# schematic.net
KiCad netlist of a schematic drawn in EAGLE
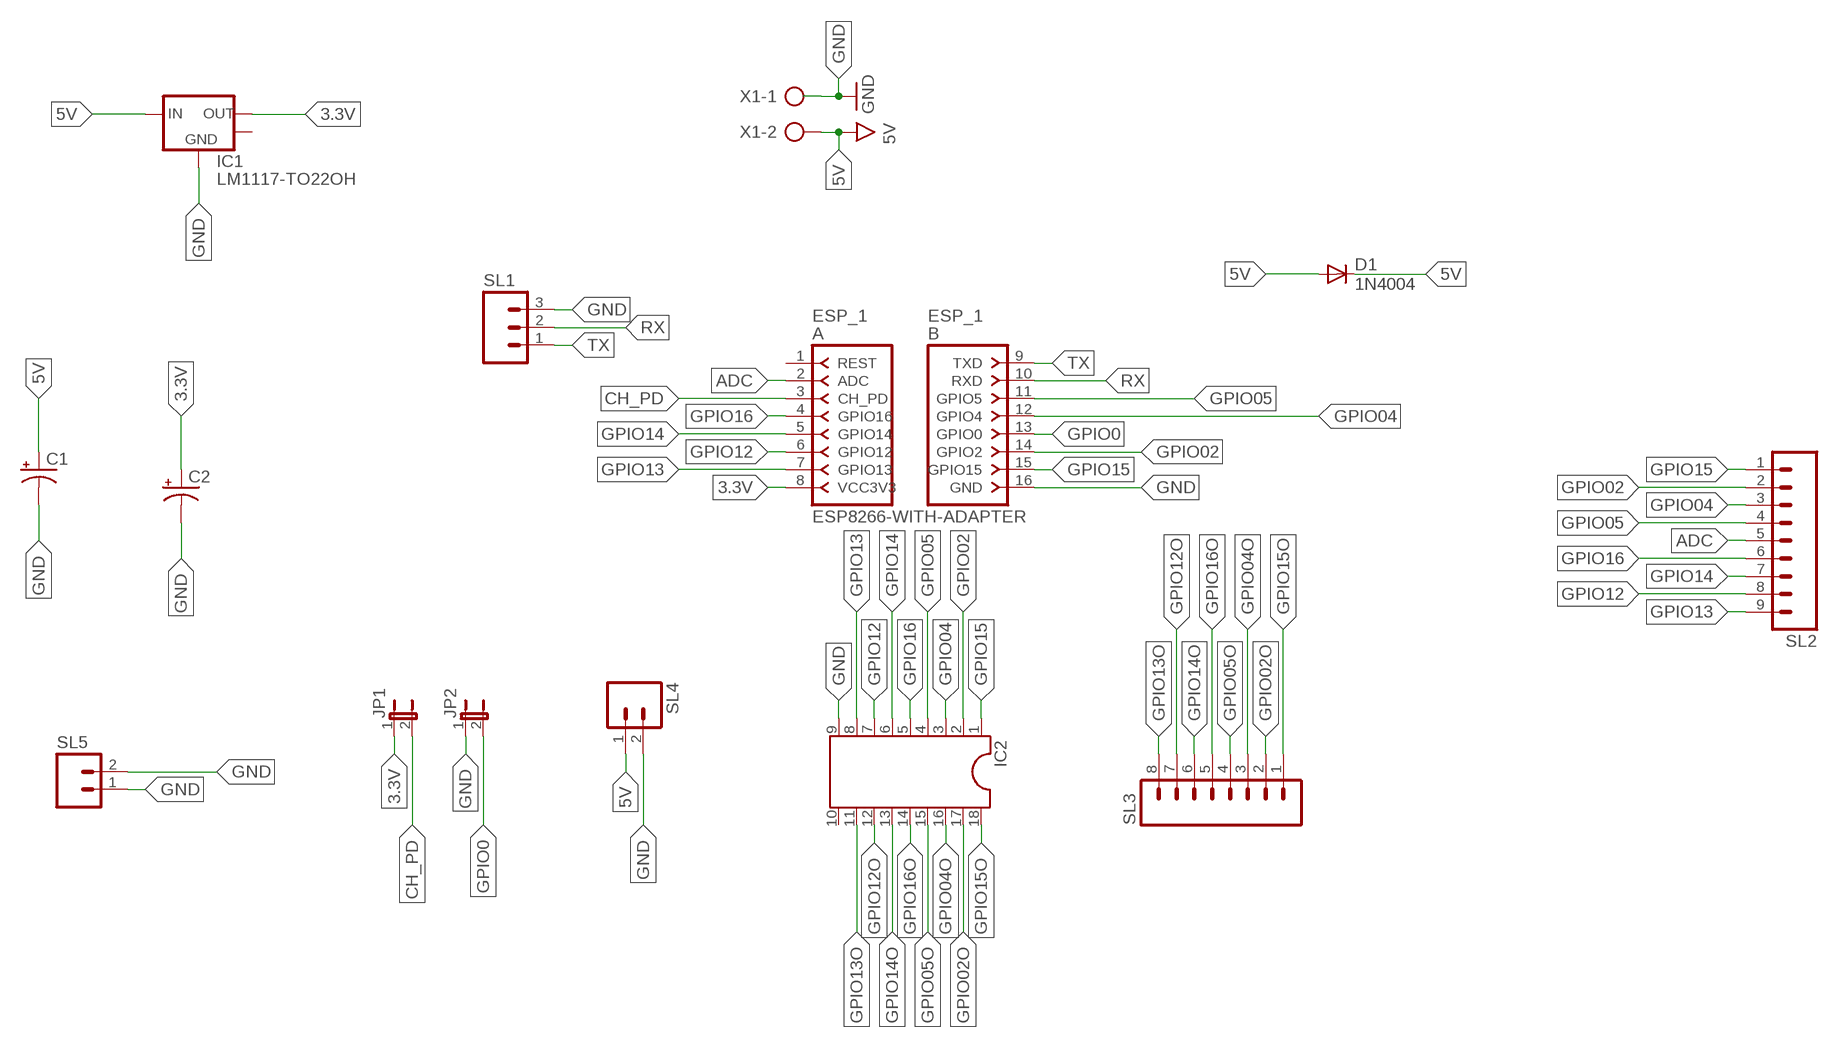
[diagram p0: schematic, sheet 1]

(export (version "E")
  (design (tool "Eeschema 10.0.6"))
  (components
    (comp (ref "C1")
      (value "CPOL-USE2-4")
      (footprint "eagle-import:E2-4")
      (libsource (lib "eagle-import") (part "CPOL-USE2-4"))
    )
    (comp (ref "C2")
      (value "CPOL-USE2-4")
      (footprint "eagle-import:E2-4")
      (libsource (lib "eagle-import") (part "CPOL-USE2-4"))
    )
    (comp (ref "D1")
      (value "1N4004")
      (footprint "eagle-import:DO41-10")
      (libsource (lib "eagle-import") (part "1N4004"))
    )
    (comp (ref "ESP_1")
      (value "ESP8266-WITH-ADAPTER")
      (footprint "eagle-import:ESP8266-ADAPTER")
      (libsource (lib "eagle-import") (part "ESP8266-WITH-ADAPTER"))
    )
    (comp (ref "IC1")
      (value "LM1117-TO22OH")
      (footprint "eagle-import:TO220L1")
      (libsource (lib "eagle-import") (part "LM1117-TO22OH"))
    )
    (comp (ref "IC2")
      (value "DIL18")
      (footprint "eagle-import:DIL18")
      (libsource (lib "eagle-import") (part "DIL18"))
    )
    (comp (ref "JP1")
      (value "JP1E")
      (footprint "eagle-import:JP1")
      (libsource (lib "eagle-import") (part "JP1E"))
    )
    (comp (ref "JP2")
      (value "JP1E")
      (footprint "eagle-import:JP1")
      (libsource (lib "eagle-import") (part "JP1E"))
    )
    (comp (ref "SL1")
      (value "M03")
      (footprint "eagle-import:03P")
      (libsource (lib "eagle-import") (part "M03"))
    )
    (comp (ref "SL2")
      (value "M09")
      (footprint "eagle-import:09P")
      (libsource (lib "eagle-import") (part "M09"))
    )
    (comp (ref "SL3")
      (value "M08")
      (footprint "eagle-import:08P")
      (libsource (lib "eagle-import") (part "M08"))
    )
    (comp (ref "SL4")
      (value "M02")
      (footprint "eagle-import:02P")
      (libsource (lib "eagle-import") (part "M02"))
    )
    (comp (ref "SL5")
      (value "M02")
      (footprint "eagle-import:02P")
      (libsource (lib "eagle-import") (part "M02"))
    )
    (comp (ref "X1")
      (value "AK500/2-H")
      (footprint "eagle-import:AK500_2-H")
      (libsource (lib "eagle-import") (part "AK500/2-H"))
    )
  )
  (nets
    (net (code "1") (name "3.3V") (class "Default")
      (node (ref "C2") (pin "+") (pinfunction "+_+") (pintype "passive"))
      (node (ref "ESP_1") (pin "8") (pinfunction "VCC3V3_8") (pintype "passive"))
      (node (ref "IC1") (pin "2") (pinfunction "VOUT_2") (pintype "bidirectional"))
      (node (ref "JP1") (pin "1") (pinfunction "1_1") (pintype "passive"))
    )
    (net (code "2") (name "5V") (class "Default")
      (node (ref "C1") (pin "+") (pinfunction "+_+") (pintype "passive"))
      (node (ref "D1") (pin "A") (pinfunction "A_A") (pintype "passive"))
      (node (ref "D1") (pin "C") (pinfunction "C_C") (pintype "passive"))
      (node (ref "IC1") (pin "3") (pinfunction "VIN_3") (pintype "bidirectional"))
      (node (ref "SL4") (pin "1") (pinfunction "1_1") (pintype "passive"))
      (node (ref "X1") (pin "2") (pinfunction "KL_2") (pintype "passive"))
    )
    (net (code "3") (name "ADC") (class "Default")
      (node (ref "ESP_1") (pin "2") (pinfunction "ADC_2") (pintype "passive"))
      (node (ref "SL2") (pin "5") (pinfunction "5_5") (pintype "passive"))
    )
    (net (code "4") (name "CH_PD") (class "Default")
      (node (ref "ESP_1") (pin "3") (pinfunction "CH_PD_3") (pintype "passive"))
      (node (ref "JP1") (pin "2") (pinfunction "2_2") (pintype "passive"))
    )
    (net (code "5") (name "GND") (class "Default")
      (node (ref "C1") (pin "-") (pinfunction "-_-") (pintype "passive"))
      (node (ref "C2") (pin "-") (pinfunction "-_-") (pintype "passive"))
      (node (ref "ESP_1") (pin "16") (pinfunction "GND_16") (pintype "passive"))
      (node (ref "IC1") (pin "1") (pinfunction "GND_1") (pintype "bidirectional"))
      (node (ref "IC2") (pin "9") (pinfunction "9_9") (pintype "passive"))
      (node (ref "JP2") (pin "1") (pinfunction "1_1") (pintype "passive"))
      (node (ref "SL1") (pin "3") (pinfunction "3_3") (pintype "passive"))
      (node (ref "SL4") (pin "2") (pinfunction "2_2") (pintype "passive"))
      (node (ref "SL5") (pin "1") (pinfunction "1_1") (pintype "passive"))
      (node (ref "SL5") (pin "2") (pinfunction "2_2") (pintype "passive"))
      (node (ref "X1") (pin "1") (pinfunction "KL_1") (pintype "passive"))
    )
    (net (code "6") (name "GPIO0") (class "Default")
      (node (ref "ESP_1") (pin "13") (pinfunction "GPIO0_13") (pintype "passive"))
      (node (ref "JP2") (pin "2") (pinfunction "2_2") (pintype "passive"))
    )
    (net (code "7") (name "GPIO02") (class "Default")
      (node (ref "ESP_1") (pin "14") (pinfunction "GPIO2_14") (pintype "passive"))
      (node (ref "IC2") (pin "2") (pinfunction "2_2") (pintype "passive"))
      (node (ref "SL2") (pin "2") (pinfunction "2_2") (pintype "passive"))
    )
    (net (code "8") (name "GPIO02O") (class "Default")
      (node (ref "IC2") (pin "17") (pinfunction "17_17") (pintype "passive"))
      (node (ref "SL3") (pin "2") (pinfunction "2_2") (pintype "passive"))
    )
    (net (code "9") (name "GPIO04") (class "Default")
      (node (ref "ESP_1") (pin "12") (pinfunction "GPIO4_12") (pintype "passive"))
      (node (ref "IC2") (pin "3") (pinfunction "3_3") (pintype "passive"))
      (node (ref "SL2") (pin "3") (pinfunction "3_3") (pintype "passive"))
    )
    (net (code "10") (name "GPIO04O") (class "Default")
      (node (ref "IC2") (pin "16") (pinfunction "16_16") (pintype "passive"))
      (node (ref "SL3") (pin "3") (pinfunction "3_3") (pintype "passive"))
    )
    (net (code "11") (name "GPIO05") (class "Default")
      (node (ref "ESP_1") (pin "11") (pinfunction "GPIO5_11") (pintype "passive"))
      (node (ref "IC2") (pin "4") (pinfunction "4_4") (pintype "passive"))
      (node (ref "SL2") (pin "4") (pinfunction "4_4") (pintype "passive"))
    )
    (net (code "12") (name "GPIO05O") (class "Default")
      (node (ref "IC2") (pin "15") (pinfunction "15_15") (pintype "passive"))
      (node (ref "SL3") (pin "4") (pinfunction "4_4") (pintype "passive"))
    )
    (net (code "13") (name "GPIO12") (class "Default")
      (node (ref "ESP_1") (pin "6") (pinfunction "GPIO12_6") (pintype "passive"))
      (node (ref "IC2") (pin "7") (pinfunction "7_7") (pintype "passive"))
      (node (ref "SL2") (pin "8") (pinfunction "8_8") (pintype "passive"))
    )
    (net (code "14") (name "GPIO12O") (class "Default")
      (node (ref "IC2") (pin "12") (pinfunction "12_12") (pintype "passive"))
      (node (ref "SL3") (pin "7") (pinfunction "7_7") (pintype "passive"))
    )
    (net (code "15") (name "GPIO13") (class "Default")
      (node (ref "ESP_1") (pin "7") (pinfunction "GPIO13_7") (pintype "passive"))
      (node (ref "IC2") (pin "8") (pinfunction "8_8") (pintype "passive"))
      (node (ref "SL2") (pin "9") (pinfunction "9_9") (pintype "passive"))
    )
    (net (code "16") (name "GPIO13O") (class "Default")
      (node (ref "IC2") (pin "11") (pinfunction "11_11") (pintype "passive"))
      (node (ref "SL3") (pin "8") (pinfunction "8_8") (pintype "passive"))
    )
    (net (code "17") (name "GPIO14") (class "Default")
      (node (ref "ESP_1") (pin "5") (pinfunction "GPIO14_5") (pintype "passive"))
      (node (ref "IC2") (pin "6") (pinfunction "6_6") (pintype "passive"))
      (node (ref "SL2") (pin "7") (pinfunction "7_7") (pintype "passive"))
    )
    (net (code "18") (name "GPIO14O") (class "Default")
      (node (ref "IC2") (pin "13") (pinfunction "13_13") (pintype "passive"))
      (node (ref "SL3") (pin "6") (pinfunction "6_6") (pintype "passive"))
    )
    (net (code "19") (name "GPIO15") (class "Default")
      (node (ref "ESP_1") (pin "15") (pinfunction "GPIO15_15") (pintype "passive"))
      (node (ref "IC2") (pin "1") (pinfunction "1_1") (pintype "passive"))
      (node (ref "SL2") (pin "1") (pinfunction "1_1") (pintype "passive"))
    )
    (net (code "20") (name "GPIO15O") (class "Default")
      (node (ref "IC2") (pin "18") (pinfunction "18_18") (pintype "passive"))
      (node (ref "SL3") (pin "1") (pinfunction "1_1") (pintype "passive"))
    )
    (net (code "21") (name "GPIO16") (class "Default")
      (node (ref "ESP_1") (pin "4") (pinfunction "GPIO16_4") (pintype "passive"))
      (node (ref "IC2") (pin "5") (pinfunction "5_5") (pintype "passive"))
      (node (ref "SL2") (pin "6") (pinfunction "6_6") (pintype "passive"))
    )
    (net (code "22") (name "GPIO16O") (class "Default")
      (node (ref "IC2") (pin "14") (pinfunction "14_14") (pintype "passive"))
      (node (ref "SL3") (pin "5") (pinfunction "5_5") (pintype "passive"))
    )
    (net (code "23") (name "RX") (class "Default")
      (node (ref "ESP_1") (pin "10") (pinfunction "RXD_10") (pintype "passive"))
      (node (ref "SL1") (pin "2") (pinfunction "2_2") (pintype "passive"))
    )
    (net (code "24") (name "TX") (class "Default")
      (node (ref "ESP_1") (pin "9") (pinfunction "TXD_9") (pintype "passive"))
      (node (ref "SL1") (pin "1") (pinfunction "1_1") (pintype "passive"))
    )
    (net (code "25") (name "unconnected-(ESP_1-REST-Pad1)") (class "Default")
      (node (ref "ESP_1") (pin "1") (pinfunction "REST_1") (pintype "passive"))
    )
    (net (code "26") (name "unconnected-(IC1-HEATSINK-Pad4)") (class "Default")
      (node (ref "IC1") (pin "4") (pinfunction "HEATSINK_4") (pintype "bidirectional"))
    )
    (net (code "27") (name "unconnected-(IC2-Pad10)") (class "Default")
      (node (ref "IC2") (pin "10") (pinfunction "10_10") (pintype "passive"))
    )
  )
)
